# max232.net
KiCad netlist of a schematic drawn in EAGLE
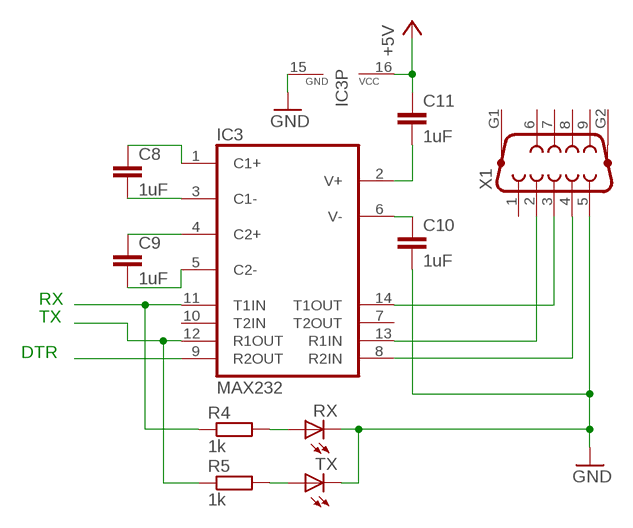
[diagram p0: schematic, sheet 1]

(export (version "E")
  (design (tool "Eeschema 10.0.6"))
  (components
    (comp (ref "C8")
      (value "1uF")
      (footprint "eagle-import:C5B3.5")
      (libsource (lib "eagle-import") (part "C5/3.5"))
    )
    (comp (ref "C9")
      (value "1uF")
      (footprint "eagle-import:C5B3.5")
      (libsource (lib "eagle-import") (part "C5/3.5"))
    )
    (comp (ref "C10")
      (value "1uF")
      (footprint "eagle-import:C5B3.5")
      (libsource (lib "eagle-import") (part "C5/3.5"))
    )
    (comp (ref "C11")
      (value "1uF")
      (footprint "eagle-import:C5B3.5")
      (libsource (lib "eagle-import") (part "C5/3.5"))
    )
    (comp (ref "IC3")
      (value "MAX232")
      (footprint "eagle-import:DIL16")
      (fields (field (name "MF") "MAXIM") (field (name "MPN") "MAX232ACPE+"))
      (libsource (lib "eagle-import") (part "MAX232"))
    )
    (comp (ref "R4")
      (value "1k")
      (footprint "eagle-import:0309_10")
      (libsource (lib "eagle-import") (part "R-EU_0309/10"))
    )
    (comp (ref "R5")
      (value "1k")
      (footprint "eagle-import:0309_10")
      (libsource (lib "eagle-import") (part "R-EU_0309/10"))
    )
    (comp (ref "RX")
      (value "LED3MM")
      (footprint "eagle-import:LED3MM")
      (libsource (lib "eagle-import") (part "LED3MM"))
    )
    (comp (ref "TX")
      (value "LED3MM")
      (footprint "eagle-import:LED3MM")
      (libsource (lib "eagle-import") (part "LED3MM"))
    )
    (comp (ref "X1")
      (value "F09HP")
      (footprint "eagle-import:F09HP")
      (libsource (lib "eagle-import") (part "F09HP"))
    )
  )
  (nets
    (net (code "1") (name "+5V") (class "Default")
      (node (ref "C11") (pin "1") (pinfunction "1_1") (pintype "passive"))
      (node (ref "IC3") (pin "16") (pinfunction "VCC_16") (pintype "power_in"))
    )
    (net (code "2") (name "GND") (class "Default")
      (node (ref "C10") (pin "2") (pinfunction "2_2") (pintype "passive"))
      (node (ref "IC3") (pin "15") (pinfunction "GND_15") (pintype "power_in"))
      (node (ref "RX") (pin "K") (pinfunction "C_K") (pintype "passive"))
      (node (ref "TX") (pin "K") (pinfunction "C_K") (pintype "passive"))
      (node (ref "X1") (pin "5") (pinfunction "5_5") (pintype "passive"))
    )
    (net (code "3") (name "Net-(IC3A-C1+)") (class "Default")
      (node (ref "C8") (pin "1") (pinfunction "1_1") (pintype "passive"))
      (node (ref "IC3") (pin "1") (pinfunction "C1+_1") (pintype "bidirectional"))
    )
    (net (code "4") (name "Net-(IC3A-C1-)") (class "Default")
      (node (ref "C8") (pin "2") (pinfunction "2_2") (pintype "passive"))
      (node (ref "IC3") (pin "3") (pinfunction "C1-_3") (pintype "bidirectional"))
    )
    (net (code "5") (name "Net-(IC3A-C2+)") (class "Default")
      (node (ref "C9") (pin "1") (pinfunction "1_1") (pintype "passive"))
      (node (ref "IC3") (pin "4") (pinfunction "C2+_4") (pintype "bidirectional"))
    )
    (net (code "6") (name "Net-(IC3A-C2-)") (class "Default")
      (node (ref "C9") (pin "2") (pinfunction "2_2") (pintype "passive"))
      (node (ref "IC3") (pin "5") (pinfunction "C2-_5") (pintype "bidirectional"))
    )
    (net (code "7") (name "Net-(IC3A-R1IN)") (class "Default")
      (node (ref "IC3") (pin "13") (pinfunction "R1IN_13") (pintype "input"))
      (node (ref "X1") (pin "2") (pinfunction "2_2") (pintype "passive"))
    )
    (net (code "8") (name "Net-(IC3A-R1OUT)") (class "Default")
      (node (ref "IC3") (pin "12") (pinfunction "R1OUT_12") (pintype "output"))
      (node (ref "R5") (pin "1") (pinfunction "1_1") (pintype "passive"))
    )
    (net (code "9") (name "Net-(IC3A-R2IN)") (class "Default")
      (node (ref "IC3") (pin "8") (pinfunction "R2IN_8") (pintype "input"))
      (node (ref "X1") (pin "4") (pinfunction "4_4") (pintype "passive"))
    )
    (net (code "10") (name "Net-(IC3A-T1IN)") (class "Default")
      (node (ref "IC3") (pin "11") (pinfunction "T1IN_11") (pintype "input"))
      (node (ref "R4") (pin "1") (pinfunction "1_1") (pintype "passive"))
    )
    (net (code "11") (name "Net-(IC3A-T1OUT)") (class "Default")
      (node (ref "IC3") (pin "14") (pinfunction "T1OUT_14") (pintype "output"))
      (node (ref "X1") (pin "3") (pinfunction "3_3") (pintype "passive"))
    )
    (net (code "12") (name "Net-(IC3A-V+)") (class "Default")
      (node (ref "C11") (pin "2") (pinfunction "2_2") (pintype "passive"))
      (node (ref "IC3") (pin "2") (pinfunction "V+_2") (pintype "bidirectional"))
    )
    (net (code "13") (name "Net-(IC3A-V-)") (class "Default")
      (node (ref "C10") (pin "1") (pinfunction "1_1") (pintype "passive"))
      (node (ref "IC3") (pin "6") (pinfunction "V-_6") (pintype "bidirectional"))
    )
    (net (code "14") (name "Net-(R4-Pad2)") (class "Default")
      (node (ref "R4") (pin "2") (pinfunction "2_2") (pintype "passive"))
      (node (ref "RX") (pin "A") (pinfunction "A_A") (pintype "passive"))
    )
    (net (code "15") (name "Net-(R5-Pad2)") (class "Default")
      (node (ref "R5") (pin "2") (pinfunction "2_2") (pintype "passive"))
      (node (ref "TX") (pin "A") (pinfunction "A_A") (pintype "passive"))
    )
    (net (code "16") (name "unconnected-(IC3A-R2OUT-Pad9)") (class "Default")
      (node (ref "IC3") (pin "9") (pinfunction "R2OUT_9") (pintype "output"))
    )
    (net (code "17") (name "unconnected-(IC3A-T2IN-Pad10)") (class "Default")
      (node (ref "IC3") (pin "10") (pinfunction "T2IN_10") (pintype "input"))
    )
    (net (code "18") (name "unconnected-(IC3A-T2OUT-Pad7)") (class "Default")
      (node (ref "IC3") (pin "7") (pinfunction "T2OUT_7") (pintype "output"))
    )
    (net (code "19") (name "unconnected-(X1-Pad1)") (class "Default")
      (node (ref "X1") (pin "1") (pinfunction "1_1") (pintype "passive"))
    )
    (net (code "20") (name "unconnected-(X1-Pad6)") (class "Default")
      (node (ref "X1") (pin "6") (pinfunction "6_6") (pintype "passive"))
    )
    (net (code "21") (name "unconnected-(X1-Pad7)") (class "Default")
      (node (ref "X1") (pin "7") (pinfunction "7_7") (pintype "passive"))
    )
    (net (code "22") (name "unconnected-(X1-Pad8)") (class "Default")
      (node (ref "X1") (pin "8") (pinfunction "8_8") (pintype "passive"))
    )
    (net (code "23") (name "unconnected-(X1-Pad9)") (class "Default")
      (node (ref "X1") (pin "9") (pinfunction "9_9") (pintype "passive"))
    )
    (net (code "24") (name "unconnected-(X1-PadG1)") (class "Default")
      (node (ref "X1") (pin "G1") (pinfunction "G1_G1") (pintype "passive"))
    )
    (net (code "25") (name "unconnected-(X1-PadG2)") (class "Default")
      (node (ref "X1") (pin "G2") (pinfunction "G2_G2") (pintype "passive"))
    )
  )
)
